# V1_2.net
KiCad netlist of a schematic drawn in Altium Designer
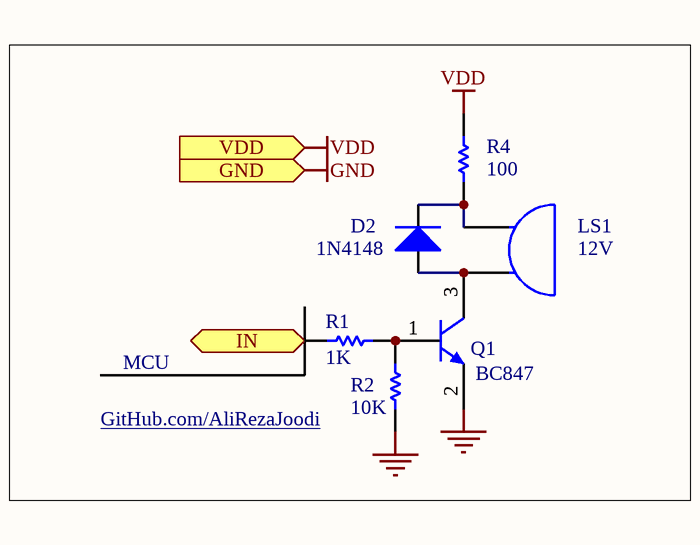
[diagram p0: V1.2.SchDoc]

(export (version "E")
  (design (tool "Eeschema 10.0.6"))
  (components
    (comp (ref "D2")
      (value "1N4148")
      (footprint "SOD-523")
      (description "Default Diode")
      (fields
        (field (name "MANUFACTURER") "Generic Components")
        (field (name "Comment") "Diode")
        (field (name "PUBLISHER") "Altium Limited")
      )
      (libsource (lib "Miscellaneous Devices") (part "Diode"))
    )
    (comp (ref "LS1")
      (value "12V")
      (footprint "RB_7.62mm")
      (description "Sounder")
      (fields
        (field (name "MANUFACTURER") "Generic Components")
        (field (name "Comment") "Buzzer")
        (field (name "PUBLISHER") "Altium Limited")
      )
      (libsource (lib "my Libraries") (part "Buzzer"))
    )
    (comp (ref "Q1")
      (value "BC847")
      (footprint "SOT23-3N")
      (description "Silicon Bipolar Transistor")
      (fields (field (name "Comment") "NPN"))
      (libsource (lib "my Libraries") (part "BC847"))
    )
    (comp (ref "R1")
      (value "1K")
      (footprint "0805")
      (description "Resistor")
      (fields (field (name "Comment") "Res1") (field (name "PUBLISHER") "Altium Limited"))
      (libsource (lib "Miscellaneous Devices") (part "Res1"))
    )
    (comp (ref "R2")
      (value "10K")
      (footprint "0805")
      (description "Resistor")
      (fields (field (name "Comment") "Res1") (field (name "PUBLISHER") "Altium Limited"))
      (libsource (lib "Miscellaneous Devices") (part "Res1"))
    )
    (comp (ref "R4")
      (value "100")
      (footprint "0805")
      (description "Resistor")
      (fields (field (name "Comment") "Res1") (field (name "PUBLISHER") "Altium Limited"))
      (libsource (lib "Miscellaneous Devices") (part "Res1"))
    )
  )
  (nets
    (net (code "1") (name "/IN") (class "Default")
      (node (ref "R1") (pin "2") (pinfunction "2_2") (pintype "passive"))
    )
    (net (code "2") (name "GND") (class "Default")
      (node (ref "Q1") (pin "2") (pinfunction "E_2") (pintype "passive"))
      (node (ref "R2") (pin "2") (pinfunction "2_2") (pintype "passive"))
    )
    (net (code "3") (name "Net-(D2-A)") (class "Default")
      (node (ref "D2") (pin "1") (pinfunction "A_1") (pintype "passive"))
      (node (ref "LS1") (pin "2") (pinfunction "B_2") (pintype "passive"))
      (node (ref "Q1") (pin "3") (pinfunction "C_3") (pintype "passive"))
    )
    (net (code "4") (name "Net-(D2-K)") (class "Default")
      (node (ref "D2") (pin "2") (pinfunction "K_2") (pintype "passive"))
      (node (ref "LS1") (pin "1") (pinfunction "A_1") (pintype "passive"))
      (node (ref "R4") (pin "1") (pinfunction "1_1") (pintype "passive"))
    )
    (net (code "5") (name "Net-(Q1-B)") (class "Default")
      (node (ref "Q1") (pin "1") (pinfunction "B_1") (pintype "passive"))
      (node (ref "R1") (pin "1") (pinfunction "1_1") (pintype "passive"))
      (node (ref "R2") (pin "1") (pinfunction "1_1") (pintype "passive"))
    )
    (net (code "6") (name "VDD") (class "Default")
      (node (ref "R4") (pin "2") (pinfunction "2_2") (pintype "passive"))
    )
  )
)
